# sv650.net
KiCad netlist of a schematic drawn in EAGLE
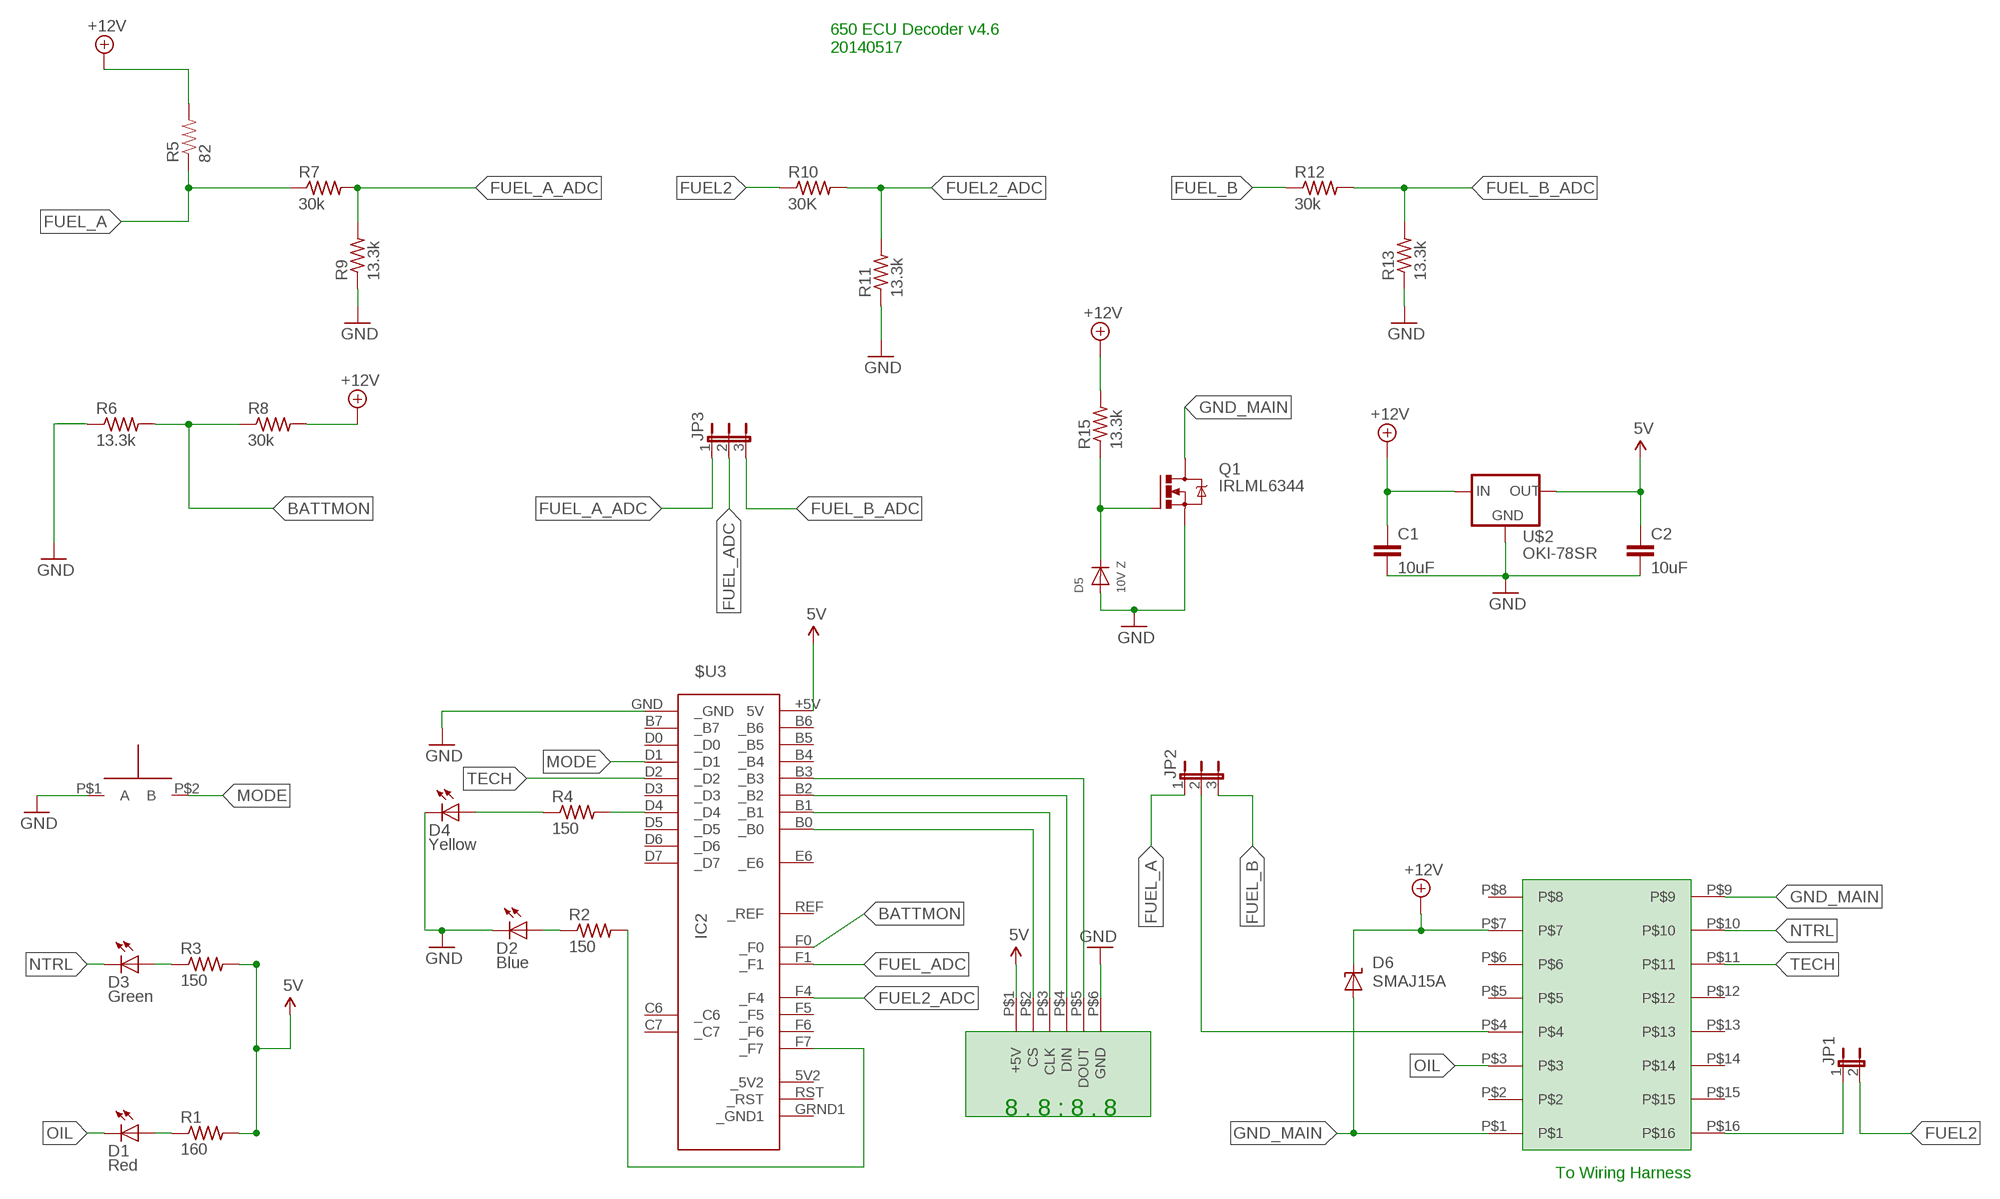
[diagram p0: schematic, sheet 1]

(export (version "E")
  (design (tool "Eeschema 10.0.6"))
  (components
    (comp (ref "$U3")
      (value "IC2")
      (footprint "eagle-import:TEENSY")
      (libsource (lib "eagle-import") (part "TEENSY"))
    )
    (comp (ref "C1")
      (value "10uF")
      (footprint "eagle-import:C0805")
      (libsource (lib "eagle-import") (part "C-EUC0805"))
    )
    (comp (ref "C2")
      (value "10uF")
      (footprint "eagle-import:C0805")
      (libsource (lib "eagle-import") (part "C-EUC0805"))
    )
    (comp (ref "D1")
      (value "Red")
      (footprint "eagle-import:LED10MM")
      (libsource (lib "eagle-import") (part "LED10MM"))
    )
    (comp (ref "D2")
      (value "Blue")
      (footprint "eagle-import:LED5MM")
      (libsource (lib "eagle-import") (part "LED5MM"))
    )
    (comp (ref "D3")
      (value "Green")
      (footprint "eagle-import:LED10MM")
      (libsource (lib "eagle-import") (part "LED10MM"))
    )
    (comp (ref "D4")
      (value "Yellow")
      (footprint "eagle-import:LED10MM")
      (libsource (lib "eagle-import") (part "LED10MM"))
    )
    (comp (ref "D5")
      (value "10V Z")
      (footprint "eagle-import:SOD-123")
      (libsource (lib "eagle-import") (part "DIODESOD-123"))
    )
    (comp (ref "D6")
      (value "SMAJ15A")
      (footprint "eagle-import:SMBG")
      (libsource (lib "eagle-import") (part "SUPPRESSOR-SMBG"))
    )
    (comp (ref "JP1")
      (value "JP1E")
      (footprint "eagle-import:JP1")
      (libsource (lib "eagle-import") (part "JP1E"))
    )
    (comp (ref "JP2")
      (value "JP2E")
      (footprint "eagle-import:JP2")
      (libsource (lib "eagle-import") (part "JP2E"))
    )
    (comp (ref "JP3")
      (value "JP2E")
      (footprint "eagle-import:JP2")
      (libsource (lib "eagle-import") (part "JP2E"))
    )
    (comp (ref "Q1")
      (value "IRLML6344")
      (footprint "eagle-import:SOT23")
      (libsource (lib "eagle-import") (part "IRLML6344"))
    )
    (comp (ref "R1")
      (value "160")
      (footprint "eagle-import:M0805")
      (fields (field (name "MF") "VISHAY/DALE") (field (name "MPN") "CRCW0805160RFKEA"))
      (libsource (lib "eagle-import") (part "R-US_M0805"))
    )
    (comp (ref "R2")
      (value "150")
      (footprint "eagle-import:M0805")
      (fields (field (name "MPN") "MCHP05W4F1500T5E"))
      (libsource (lib "eagle-import") (part "R-US_M0805"))
    )
    (comp (ref "R3")
      (value "150")
      (footprint "eagle-import:M0805")
      (fields (field (name "MPN") "MCHP05W4F1500T5E"))
      (libsource (lib "eagle-import") (part "R-US_M0805"))
    )
    (comp (ref "R4")
      (value "150")
      (footprint "eagle-import:M0805")
      (fields (field (name "MPN") "MCHP05W4F1500T5E"))
      (libsource (lib "eagle-import") (part "R-US_M0805"))
    )
    (comp (ref "R5")
      (value "82")
      (footprint "eagle-import:AXIAL-0.9")
      (libsource (lib "eagle-import") (part "RESISTORPTH-5W"))
    )
    (comp (ref "R6")
      (value "13.3k")
      (footprint "eagle-import:M0805")
      (fields (field (name "MF") "VISHAY/DALE") (field (name "MPN") "CRCW080510K0FKTA"))
      (libsource (lib "eagle-import") (part "R-US_M0805"))
    )
    (comp (ref "R7")
      (value "30k")
      (footprint "eagle-import:M0805")
      (libsource (lib "eagle-import") (part "R-US_M0805"))
    )
    (comp (ref "R8")
      (value "30k")
      (footprint "eagle-import:M0805")
      (fields (field (name "MF") "VISHAY/DALE") (field (name "MPN") "CRCW080510K0FKTA"))
      (libsource (lib "eagle-import") (part "R-US_M0805"))
    )
    (comp (ref "R9")
      (value "13.3k")
      (footprint "eagle-import:M0805")
      (libsource (lib "eagle-import") (part "R-US_M0805"))
    )
    (comp (ref "R10")
      (value "30K")
      (footprint "eagle-import:M0805")
      (libsource (lib "eagle-import") (part "R-US_M0805"))
    )
    (comp (ref "R11")
      (value "13.3k")
      (footprint "eagle-import:M0805")
      (libsource (lib "eagle-import") (part "R-US_M0805"))
    )
    (comp (ref "R12")
      (value "30k")
      (footprint "eagle-import:M0805")
      (libsource (lib "eagle-import") (part "R-US_M0805"))
    )
    (comp (ref "R13")
      (value "13.3k")
      (footprint "eagle-import:M0805")
      (libsource (lib "eagle-import") (part "R-US_M0805"))
    )
    (comp (ref "R15")
      (value "13.3k")
      (footprint "eagle-import:M0805")
      (libsource (lib "eagle-import") (part "R-US_M0805"))
    )
    (comp (ref "U$1")
      (value "OASIS-7-SEG-DISPLAY")
      (footprint "eagle-import:OASIS-7-SEG-DISPLAY")
      (libsource (lib "eagle-import") (part "OASIS-7-SEG-DISPLAY"))
    )
    (comp (ref "U$2")
      (value "OKI-78SR")
      (footprint "eagle-import:OKI-78SR-H")
      (libsource (lib "eagle-import") (part "OKI-78SR"))
    )
    (comp (ref "U$3")
      (value "TE-174975-2")
      (footprint "eagle-import:TE-174975-2")
      (libsource (lib "eagle-import") (part "TE-174975-2"))
    )
    (comp (ref "U$10")
      (value "R13-509A-05-BB/R13-509A-05-BR")
      (footprint "eagle-import:R13-509A-05-BB_R13-509A-05-BR")
      (libsource (lib "eagle-import") (part "R13-509A-05-BB/R13-509A-05-BR"))
    )
  )
  (nets
    (net (code "1") (name "+12V") (class "Default")
      (node (ref "C1") (pin "1") (pinfunction "1_1") (pintype "passive"))
      (node (ref "D6") (pin "C") (pinfunction "C_C") (pintype "passive"))
      (node (ref "R15") (pin "2") (pinfunction "2_2") (pintype "passive"))
      (node (ref "R5") (pin "P$2") (pinfunction "2_P$2") (pintype "passive"))
      (node (ref "R8") (pin "2") (pinfunction "2_2") (pintype "passive"))
      (node (ref "U$2") (pin "P$1") (pinfunction "IN_P$1") (pintype "input"))
      (node (ref "U$3") (pin "P$7") (pinfunction "P$7_P$7") (pintype "bidirectional"))
    )
    (net (code "2") (name "5V") (class "Default")
      (node (ref "$U3") (pin "+5V") (pinfunction "5V_+5V") (pintype "bidirectional"))
      (node (ref "C2") (pin "1") (pinfunction "1_1") (pintype "passive"))
      (node (ref "R1") (pin "2") (pinfunction "2_2") (pintype "passive"))
      (node (ref "R3") (pin "2") (pinfunction "2_2") (pintype "passive"))
      (node (ref "U$1") (pin "P$1") (pinfunction "+5V_P$1") (pintype "bidirectional"))
      (node (ref "U$2") (pin "P$3") (pinfunction "OUT_P$3") (pintype "input"))
    )
    (net (code "3") (name "BATTMON") (class "Default")
      (node (ref "$U3") (pin "F0") (pinfunction "_F0_F0") (pintype "bidirectional"))
      (node (ref "R6") (pin "2") (pinfunction "2_2") (pintype "passive"))
      (node (ref "R8") (pin "1") (pinfunction "1_1") (pintype "passive"))
    )
    (net (code "4") (name "FUEL2") (class "Default")
      (node (ref "JP1") (pin "2") (pinfunction "2_2") (pintype "passive"))
      (node (ref "R10") (pin "1") (pinfunction "1_1") (pintype "passive"))
    )
    (net (code "5") (name "FUEL2_ADC") (class "Default")
      (node (ref "$U3") (pin "F4") (pinfunction "_F4_F4") (pintype "bidirectional"))
      (node (ref "R10") (pin "2") (pinfunction "2_2") (pintype "passive"))
      (node (ref "R11") (pin "2") (pinfunction "2_2") (pintype "passive"))
    )
    (net (code "6") (name "FUEL_A") (class "Default")
      (node (ref "JP2") (pin "1") (pinfunction "1_1") (pintype "passive"))
      (node (ref "R5") (pin "P$1") (pinfunction "1_P$1") (pintype "passive"))
      (node (ref "R7") (pin "1") (pinfunction "1_1") (pintype "passive"))
    )
    (net (code "7") (name "FUEL_ADC") (class "Default")
      (node (ref "$U3") (pin "F1") (pinfunction "_F1_F1") (pintype "bidirectional"))
      (node (ref "JP3") (pin "2") (pinfunction "2_2") (pintype "passive"))
    )
    (net (code "8") (name "FUEL_A_ADC") (class "Default")
      (node (ref "JP3") (pin "1") (pinfunction "1_1") (pintype "passive"))
      (node (ref "R7") (pin "2") (pinfunction "2_2") (pintype "passive"))
      (node (ref "R9") (pin "2") (pinfunction "2_2") (pintype "passive"))
    )
    (net (code "9") (name "FUEL_B") (class "Default")
      (node (ref "JP2") (pin "3") (pinfunction "3_3") (pintype "passive"))
      (node (ref "R12") (pin "1") (pinfunction "1_1") (pintype "passive"))
    )
    (net (code "10") (name "FUEL_B_ADC") (class "Default")
      (node (ref "JP3") (pin "3") (pinfunction "3_3") (pintype "passive"))
      (node (ref "R12") (pin "2") (pinfunction "2_2") (pintype "passive"))
      (node (ref "R13") (pin "2") (pinfunction "2_2") (pintype "passive"))
    )
    (net (code "11") (name "GND") (class "Default")
      (node (ref "$U3") (pin "GND") (pinfunction "_GND_GND") (pintype "bidirectional"))
      (node (ref "C1") (pin "2") (pinfunction "2_2") (pintype "passive"))
      (node (ref "C2") (pin "2") (pinfunction "2_2") (pintype "passive"))
      (node (ref "D2") (pin "K") (pinfunction "C_K") (pintype "passive"))
      (node (ref "D4") (pin "K") (pinfunction "C_K") (pintype "passive"))
      (node (ref "D5") (pin "A") (pinfunction "A_A") (pintype "passive"))
      (node (ref "Q1") (pin "2") (pinfunction "S_2") (pintype "passive"))
      (node (ref "R11") (pin "1") (pinfunction "1_1") (pintype "passive"))
      (node (ref "R13") (pin "1") (pinfunction "1_1") (pintype "passive"))
      (node (ref "R6") (pin "1") (pinfunction "1_1") (pintype "passive"))
      (node (ref "R9") (pin "1") (pinfunction "1_1") (pintype "passive"))
      (node (ref "U$1") (pin "P$6") (pinfunction "GND_P$6") (pintype "bidirectional"))
      (node (ref "U$10") (pin "P$1") (pinfunction "A_P$1") (pintype "passive"))
      (node (ref "U$2") (pin "P$2") (pinfunction "GND_P$2") (pintype "input"))
    )
    (net (code "12") (name "GND_MAIN") (class "Default")
      (node (ref "D6") (pin "A") (pinfunction "A_A") (pintype "passive"))
      (node (ref "Q1") (pin "3") (pinfunction "D_3") (pintype "passive"))
      (node (ref "U$3") (pin "P$1") (pinfunction "P$1_P$1") (pintype "bidirectional"))
      (node (ref "U$3") (pin "P$9") (pinfunction "P$9_P$9") (pintype "bidirectional"))
    )
    (net (code "13") (name "MODE") (class "Default")
      (node (ref "$U3") (pin "D1") (pinfunction "_D1_D1") (pintype "bidirectional"))
      (node (ref "U$10") (pin "P$2") (pinfunction "B_P$2") (pintype "passive"))
    )
    (net (code "14") (name "NTRL") (class "Default")
      (node (ref "D3") (pin "K") (pinfunction "C_K") (pintype "passive"))
      (node (ref "U$3") (pin "P$10") (pinfunction "P$10_P$10") (pintype "bidirectional"))
    )
    (net (code "15") (name "Net-($U3-_B0)") (class "Default")
      (node (ref "$U3") (pin "B0") (pinfunction "_B0_B0") (pintype "bidirectional"))
      (node (ref "U$1") (pin "P$2") (pinfunction "CS_P$2") (pintype "bidirectional"))
    )
    (net (code "16") (name "Net-($U3-_B1)") (class "Default")
      (node (ref "$U3") (pin "B1") (pinfunction "_B1_B1") (pintype "bidirectional"))
      (node (ref "U$1") (pin "P$3") (pinfunction "CLK_P$3") (pintype "bidirectional"))
    )
    (net (code "17") (name "Net-($U3-_B2)") (class "Default")
      (node (ref "$U3") (pin "B2") (pinfunction "_B2_B2") (pintype "bidirectional"))
      (node (ref "U$1") (pin "P$4") (pinfunction "DIN_P$4") (pintype "bidirectional"))
    )
    (net (code "18") (name "Net-($U3-_B3)") (class "Default")
      (node (ref "$U3") (pin "B3") (pinfunction "_B3_B3") (pintype "bidirectional"))
      (node (ref "U$1") (pin "P$5") (pinfunction "DOUT_P$5") (pintype "bidirectional"))
    )
    (net (code "19") (name "Net-($U3-_D4)") (class "Default")
      (node (ref "$U3") (pin "D4") (pinfunction "_D4_D4") (pintype "bidirectional"))
      (node (ref "R4") (pin "2") (pinfunction "2_2") (pintype "passive"))
    )
    (net (code "20") (name "Net-($U3-_F7)") (class "Default")
      (node (ref "$U3") (pin "F7") (pinfunction "_F7_F7") (pintype "bidirectional"))
      (node (ref "R2") (pin "2") (pinfunction "2_2") (pintype "passive"))
    )
    (net (code "21") (name "Net-(D1-PadA)") (class "Default")
      (node (ref "D1") (pin "A") (pinfunction "A_A") (pintype "passive"))
      (node (ref "R1") (pin "1") (pinfunction "1_1") (pintype "passive"))
    )
    (net (code "22") (name "Net-(D2-PadA)") (class "Default")
      (node (ref "D2") (pin "A") (pinfunction "A_A") (pintype "passive"))
      (node (ref "R2") (pin "1") (pinfunction "1_1") (pintype "passive"))
    )
    (net (code "23") (name "Net-(D3-PadA)") (class "Default")
      (node (ref "D3") (pin "A") (pinfunction "A_A") (pintype "passive"))
      (node (ref "R3") (pin "1") (pinfunction "1_1") (pintype "passive"))
    )
    (net (code "24") (name "Net-(D4-PadA)") (class "Default")
      (node (ref "D4") (pin "A") (pinfunction "A_A") (pintype "passive"))
      (node (ref "R4") (pin "1") (pinfunction "1_1") (pintype "passive"))
    )
    (net (code "25") (name "Net-(JP1-Pad1)") (class "Default")
      (node (ref "JP1") (pin "1") (pinfunction "1_1") (pintype "passive"))
      (node (ref "U$3") (pin "P$16") (pinfunction "P$16_P$16") (pintype "bidirectional"))
    )
    (net (code "26") (name "Net-(JP2-Pad2)") (class "Default")
      (node (ref "JP2") (pin "2") (pinfunction "2_2") (pintype "passive"))
      (node (ref "U$3") (pin "P$4") (pinfunction "P$4_P$4") (pintype "bidirectional"))
    )
    (net (code "27") (name "Net-(Q1-G)") (class "Default")
      (node (ref "D5") (pin "C") (pinfunction "C_C") (pintype "passive"))
      (node (ref "Q1") (pin "1") (pinfunction "G_1") (pintype "passive"))
      (node (ref "R15") (pin "1") (pinfunction "1_1") (pintype "passive"))
    )
    (net (code "28") (name "OIL") (class "Default")
      (node (ref "D1") (pin "K") (pinfunction "C_K") (pintype "passive"))
      (node (ref "U$3") (pin "P$3") (pinfunction "P$3_P$3") (pintype "bidirectional"))
    )
    (net (code "29") (name "TECH") (class "Default")
      (node (ref "$U3") (pin "D2") (pinfunction "_D2_D2") (pintype "bidirectional"))
      (node (ref "U$3") (pin "P$11") (pinfunction "P$11_P$11") (pintype "bidirectional"))
    )
    (net (code "30") (name "unconnected-($U3-_5V2-Pad5V2)") (class "Default")
      (node (ref "$U3") (pin "5V2") (pinfunction "_5V2_5V2") (pintype "bidirectional"))
    )
    (net (code "31") (name "unconnected-($U3-_B4-PadB4)") (class "Default")
      (node (ref "$U3") (pin "B4") (pinfunction "_B4_B4") (pintype "bidirectional"))
    )
    (net (code "32") (name "unconnected-($U3-_B5-PadB5)") (class "Default")
      (node (ref "$U3") (pin "B5") (pinfunction "_B5_B5") (pintype "bidirectional"))
    )
    (net (code "33") (name "unconnected-($U3-_B6-PadB6)") (class "Default")
      (node (ref "$U3") (pin "B6") (pinfunction "_B6_B6") (pintype "bidirectional"))
    )
    (net (code "34") (name "unconnected-($U3-_B7-PadB7)") (class "Default")
      (node (ref "$U3") (pin "B7") (pinfunction "_B7_B7") (pintype "bidirectional"))
    )
    (net (code "35") (name "unconnected-($U3-_C6-PadC6)") (class "Default")
      (node (ref "$U3") (pin "C6") (pinfunction "_C6_C6") (pintype "bidirectional"))
    )
    (net (code "36") (name "unconnected-($U3-_C7-PadC7)") (class "Default")
      (node (ref "$U3") (pin "C7") (pinfunction "_C7_C7") (pintype "bidirectional"))
    )
    (net (code "37") (name "unconnected-($U3-_D0-PadD0)") (class "Default")
      (node (ref "$U3") (pin "D0") (pinfunction "_D0_D0") (pintype "bidirectional"))
    )
    (net (code "38") (name "unconnected-($U3-_D3-PadD3)") (class "Default")
      (node (ref "$U3") (pin "D3") (pinfunction "_D3_D3") (pintype "bidirectional"))
    )
    (net (code "39") (name "unconnected-($U3-_D5-PadD5)") (class "Default")
      (node (ref "$U3") (pin "D5") (pinfunction "_D5_D5") (pintype "bidirectional"))
    )
    (net (code "40") (name "unconnected-($U3-_D6-PadD6)") (class "Default")
      (node (ref "$U3") (pin "D6") (pinfunction "_D6_D6") (pintype "bidirectional"))
    )
    (net (code "41") (name "unconnected-($U3-_D7-PadD7)") (class "Default")
      (node (ref "$U3") (pin "D7") (pinfunction "_D7_D7") (pintype "bidirectional"))
    )
    (net (code "42") (name "unconnected-($U3-_E6-PadE6)") (class "Default")
      (node (ref "$U3") (pin "E6") (pinfunction "_E6_E6") (pintype "bidirectional"))
    )
    (net (code "43") (name "unconnected-($U3-_F5-PadF5)") (class "Default")
      (node (ref "$U3") (pin "F5") (pinfunction "_F5_F5") (pintype "bidirectional"))
    )
    (net (code "44") (name "unconnected-($U3-_F6-PadF6)") (class "Default")
      (node (ref "$U3") (pin "F6") (pinfunction "_F6_F6") (pintype "bidirectional"))
    )
    (net (code "45") (name "unconnected-($U3-_GND1-PadGRND1)") (class "Default")
      (node (ref "$U3") (pin "GRND1") (pinfunction "_GND1_GRND1") (pintype "bidirectional"))
    )
    (net (code "46") (name "unconnected-($U3-_REF-PadREF)") (class "Default")
      (node (ref "$U3") (pin "REF") (pinfunction "_REF_REF") (pintype "bidirectional"))
    )
    (net (code "47") (name "unconnected-($U3-_RST-PadRST)") (class "Default")
      (node (ref "$U3") (pin "RST") (pinfunction "_RST_RST") (pintype "bidirectional"))
    )
    (net (code "48") (name "unconnected-(U$3-PadP$2)") (class "Default")
      (node (ref "U$3") (pin "P$2") (pinfunction "P$2_P$2") (pintype "bidirectional"))
    )
    (net (code "49") (name "unconnected-(U$3-PadP$5)") (class "Default")
      (node (ref "U$3") (pin "P$5") (pinfunction "P$5_P$5") (pintype "bidirectional"))
    )
    (net (code "50") (name "unconnected-(U$3-PadP$6)") (class "Default")
      (node (ref "U$3") (pin "P$6") (pinfunction "P$6_P$6") (pintype "bidirectional"))
    )
    (net (code "51") (name "unconnected-(U$3-PadP$8)") (class "Default")
      (node (ref "U$3") (pin "P$8") (pinfunction "P$8_P$8") (pintype "bidirectional"))
    )
    (net (code "52") (name "unconnected-(U$3-PadP$12)") (class "Default")
      (node (ref "U$3") (pin "P$12") (pinfunction "P$12_P$12") (pintype "bidirectional"))
    )
    (net (code "53") (name "unconnected-(U$3-PadP$13)") (class "Default")
      (node (ref "U$3") (pin "P$13") (pinfunction "P$13_P$13") (pintype "bidirectional"))
    )
    (net (code "54") (name "unconnected-(U$3-PadP$14)") (class "Default")
      (node (ref "U$3") (pin "P$14") (pinfunction "P$14_P$14") (pintype "bidirectional"))
    )
    (net (code "55") (name "unconnected-(U$3-PadP$15)") (class "Default")
      (node (ref "U$3") (pin "P$15") (pinfunction "P$15_P$15") (pintype "bidirectional"))
    )
  )
)
